# WifiNode_Pwr.net
KiCad netlist of a schematic drawn in Altium Designer
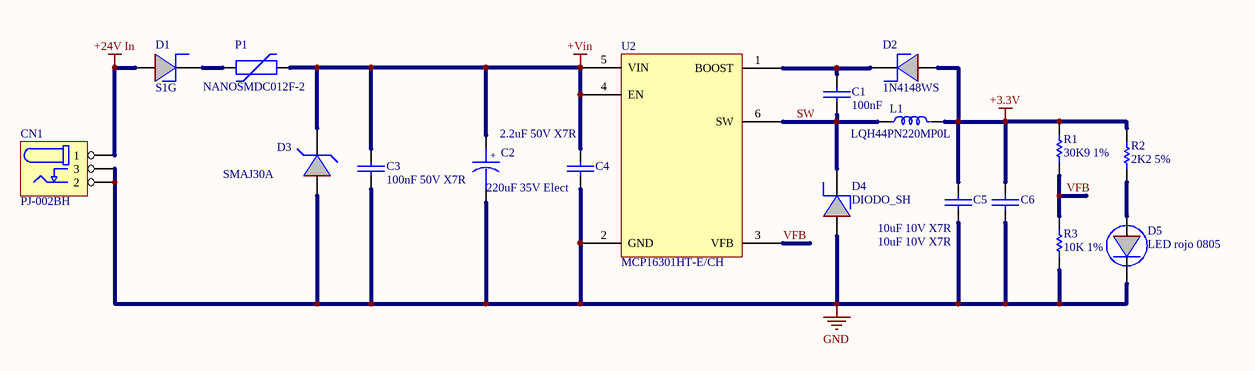
[diagram p0: WifiNode_Pwr.SchDoc]

(export (version "E")
  (design (tool "Eeschema 10.0.6"))
  (components
    (comp (ref "C1")
      (value "100nF")
      (footprint "C_0805")
      (description "Non Polarized Capacitor")
      (libsource (lib "WifiNode") (part "CAP"))
    )
    (comp (ref "C2")
      (value "220uF 35V Elect")
      (footprint "C_RAD_0.135_H_8X12_S")
      (description "Polarized Capacitor")
      (libsource (lib "WifiNode") (part "CAP_P"))
    )
    (comp (ref "C3")
      (value "100nF 50V X7R")
      (footprint "C_0805")
      (description "Non Polarized Capacitor")
      (libsource (lib "WifiNode") (part "CAP"))
    )
    (comp (ref "C4")
      (value "2.2uF 50V X7R")
      (footprint "C_0805")
      (description "Non Polarized Capacitor")
      (libsource (lib "WifiNode") (part "CAP"))
    )
    (comp (ref "C5")
      (value "10uF 10V X7R")
      (footprint "C_0805")
      (description "Non Polarized Capacitor")
      (libsource (lib "WifiNode") (part "CAP"))
    )
    (comp (ref "C6")
      (value "10uF 10V X7R")
      (footprint "C_0805")
      (description "Non Polarized Capacitor")
      (libsource (lib "WifiNode") (part "CAP"))
    )
    (comp (ref "CN1")
      (value "PJ-002BH")
      (footprint "PJ002B")
      (description "Barrel Power Connector")
      (libsource (lib "WifiNode") (part "CN_PowerJack"))
    )
    (comp (ref "D1")
      (value "S1G")
      (footprint "D_SMA")
      (description "Diode Shottky")
      (libsource (lib "WifiNode") (part "DIODO_SH"))
    )
    (comp (ref "D2")
      (value "1N4148WS")
      (footprint "D_SMA")
      (description "Diode Shottky")
      (libsource (lib "") (part "DIODO_SH_1"))
    )
    (comp (ref "D3")
      (value "SMAJ30A")
      (footprint "D_SMA")
      (description "Unidirectional TVS")
      (libsource (lib "WifiNode") (part "DIODE_TVS"))
    )
    (comp (ref "D4")
      (value "DIODO_SH")
      (footprint "D_SMA")
      (description "Diode Shottky")
      (libsource (lib "") (part "DIODO_SH_1"))
    )
    (comp (ref "D5")
      (value "LED rojo 0805")
      (footprint "D_0805")
      (description "LED")
      (libsource (lib "WifiNode") (part "LED"))
    )
    (comp (ref "L1")
      (value "LQH44PN220MP0L")
      (footprint "LQH44")
      (description "Inductor")
      (libsource (lib "WifiNode") (part "IND"))
    )
    (comp (ref "P1")
      (value "NANOSMDC012F-2")
      (footprint "NANOSMDC")
      (description "Polyswitch")
      (libsource (lib "WifiNode") (part "PLYSW"))
    )
    (comp (ref "R1")
      (value "30K9 1%")
      (footprint "R_0805")
      (description "Resistor")
      (libsource (lib "WifiNode") (part "Res1"))
    )
    (comp (ref "R2")
      (value "2K2 5%")
      (footprint "R_0805")
      (description "Resistor")
      (libsource (lib "WifiNode") (part "Res1"))
    )
    (comp (ref "R3")
      (value "10K 1%")
      (footprint "R_0805")
      (description "Resistor")
      (libsource (lib "WifiNode") (part "Res1"))
    )
    (comp (ref "U2")
      (value "MCP16301HT-E/CH")
      (footprint "SOT23-6")
      (description "Buck 36V-adj 600mA SOT-6")
      (libsource (lib "WifiNode") (part "MCP16301"))
    )
  )
  (nets
    (net (code "1") (name "+3.3V") (class "Default")
      (node (ref "C5") (pin "1") (pinfunction "1_1") (pintype "passive"))
      (node (ref "C6") (pin "1") (pinfunction "1_1") (pintype "passive"))
      (node (ref "D2") (pin "1") (pinfunction "A_1") (pintype "passive"))
      (node (ref "L1") (pin "2") (pinfunction "2_2") (pintype "passive"))
      (node (ref "R1") (pin "2") (pinfunction "2_2") (pintype "passive"))
      (node (ref "R2") (pin "2") (pinfunction "2_2") (pintype "passive"))
    )
    (net (code "2") (name "+24V In") (class "Default")
      (node (ref "CN1") (pin "1") (pinfunction "1_1") (pintype "passive"))
      (node (ref "D1") (pin "1") (pinfunction "A_1") (pintype "passive"))
    )
    (net (code "3") (name "+Vin") (class "Default")
      (node (ref "C2") (pin "1") (pinfunction "1_1") (pintype "passive"))
      (node (ref "C3") (pin "1") (pinfunction "1_1") (pintype "passive"))
      (node (ref "C4") (pin "1") (pinfunction "1_1") (pintype "passive"))
      (node (ref "D3") (pin "2") (pinfunction "K_2") (pintype "passive"))
      (node (ref "P1") (pin "2") (pinfunction "2_2") (pintype "passive"))
      (node (ref "U2") (pin "4") (pinfunction "EN_4") (pintype "passive"))
      (node (ref "U2") (pin "5") (pinfunction "VIN_5") (pintype "passive"))
    )
    (net (code "4") (name "/SW") (class "Default")
      (node (ref "C1") (pin "2") (pinfunction "2_2") (pintype "passive"))
      (node (ref "D4") (pin "2") (pinfunction "K_2") (pintype "passive"))
      (node (ref "L1") (pin "1") (pinfunction "1_1") (pintype "passive"))
      (node (ref "U2") (pin "6") (pinfunction "SW_6") (pintype "passive"))
    )
    (net (code "5") (name "/VFB") (class "Default")
      (node (ref "R1") (pin "1") (pinfunction "1_1") (pintype "passive"))
      (node (ref "R3") (pin "2") (pinfunction "2_2") (pintype "passive"))
      (node (ref "U2") (pin "3") (pinfunction "VFB_3") (pintype "passive"))
    )
    (net (code "6") (name "GND") (class "Default")
      (node (ref "C2") (pin "2") (pinfunction "2_2") (pintype "passive"))
      (node (ref "C3") (pin "2") (pinfunction "2_2") (pintype "passive"))
      (node (ref "C4") (pin "2") (pinfunction "2_2") (pintype "passive"))
      (node (ref "C5") (pin "2") (pinfunction "2_2") (pintype "passive"))
      (node (ref "C6") (pin "2") (pinfunction "2_2") (pintype "passive"))
      (node (ref "CN1") (pin "2") (pinfunction "2_2") (pintype "passive"))
      (node (ref "CN1") (pin "3") (pinfunction "3_3") (pintype "passive"))
      (node (ref "D3") (pin "1") (pinfunction "A_1") (pintype "passive"))
      (node (ref "D4") (pin "1") (pinfunction "A_1") (pintype "passive"))
      (node (ref "D5") (pin "2") (pinfunction "K_2") (pintype "passive"))
      (node (ref "R3") (pin "1") (pinfunction "1_1") (pintype "passive"))
      (node (ref "U2") (pin "2") (pinfunction "GND_2") (pintype "passive"))
    )
    (net (code "7") (name "Net-(D1-K)") (class "Default")
      (node (ref "D1") (pin "2") (pinfunction "K_2") (pintype "passive"))
      (node (ref "P1") (pin "1") (pinfunction "1_1") (pintype "passive"))
    )
    (net (code "8") (name "Net-(D2-K)") (class "Default")
      (node (ref "C1") (pin "1") (pinfunction "1_1") (pintype "passive"))
      (node (ref "D2") (pin "2") (pinfunction "K_2") (pintype "passive"))
      (node (ref "U2") (pin "1") (pinfunction "BOOST_1") (pintype "passive"))
    )
    (net (code "9") (name "Net-(D5-A)") (class "Default")
      (node (ref "D5") (pin "1") (pinfunction "A_1") (pintype "passive"))
      (node (ref "R2") (pin "1") (pinfunction "1_1") (pintype "passive"))
    )
  )
)
